# double_sided_pcb.net
KiCad netlist of a schematic drawn in EAGLE
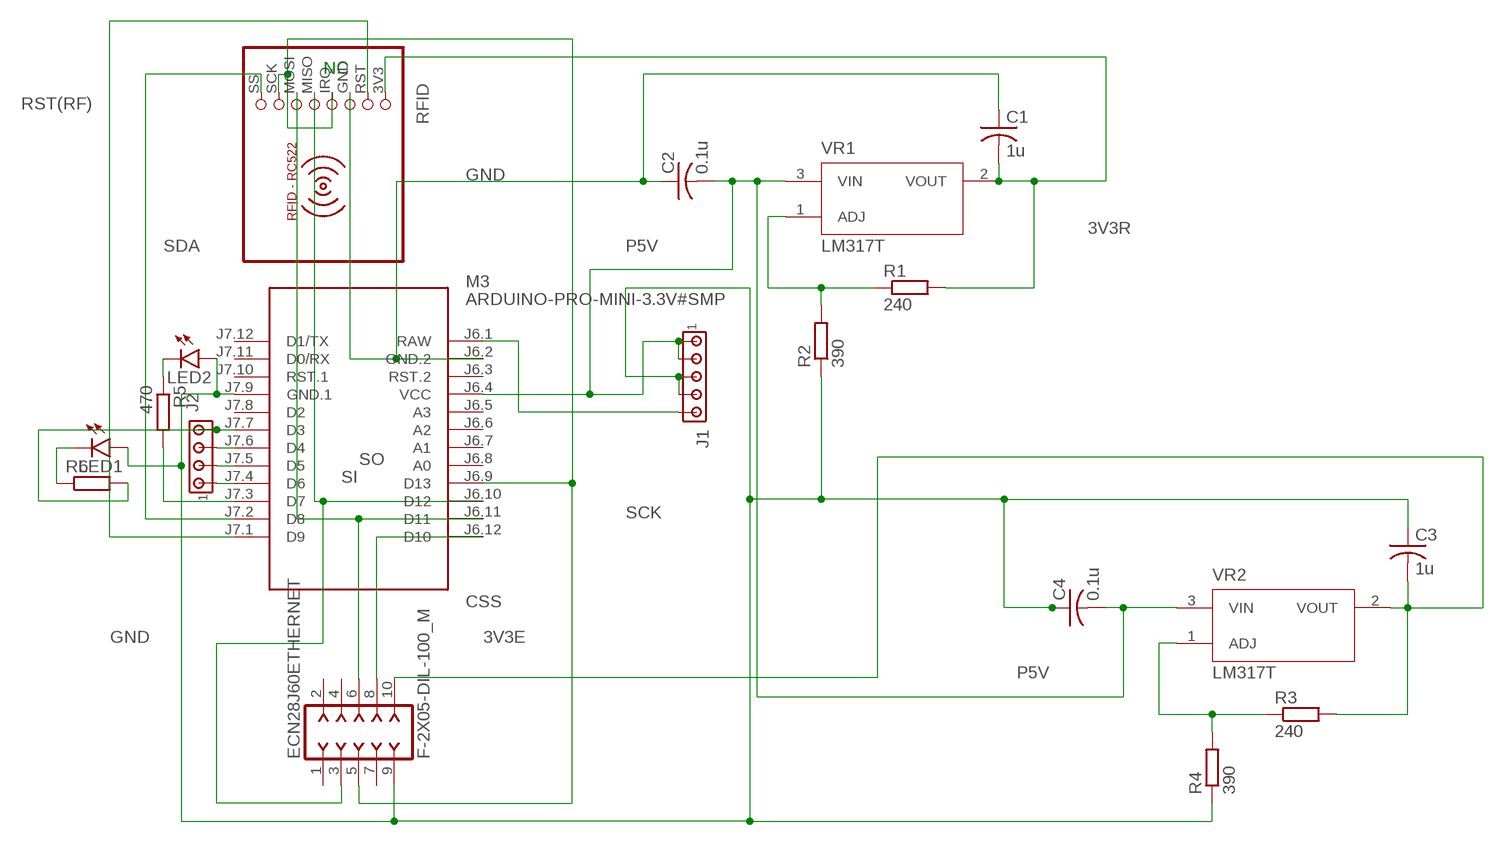
[diagram p0: schematic, sheet 1]

(export (version "E")
  (design (tool "Eeschema 10.0.6"))
  (components
    (comp (ref "C1")
      (value "1u")
      (footprint "eagle-import:C025-025X050")
      (libsource (lib "eagle-import") (part "C-US025-025X050"))
    )
    (comp (ref "C2")
      (value "0.1u")
      (footprint "eagle-import:C025-025X050")
      (libsource (lib "eagle-import") (part "C-US025-025X050"))
    )
    (comp (ref "C3")
      (value "1u")
      (footprint "eagle-import:C025-025X050")
      (libsource (lib "eagle-import") (part "C-US025-025X050"))
    )
    (comp (ref "C4")
      (value "0.1u")
      (footprint "eagle-import:C025-025X050")
      (libsource (lib "eagle-import") (part "C-US025-025X050"))
    )
    (comp (ref "ECN28J60ETHERNET")
      (value "F-2X05-DIL-100_M")
      (footprint "eagle-import:DIL-100-2X05_M")
      (libsource (lib "eagle-import") (part "F-2X05-DIL-100_M"))
    )
    (comp (ref "J1")
      (value "MTA05-100")
      (footprint "eagle-import:10X05MTA")
      (libsource (lib "eagle-import") (part "MTA05-100"))
    )
    (comp (ref "J2")
      (value "MTA04-100")
      (footprint "eagle-import:10X04MTA")
      (libsource (lib "eagle-import") (part "MTA04-100"))
    )
    (comp (ref "LED1")
      (value "LED3MM")
      (footprint "eagle-import:LED3MM")
      (libsource (lib "eagle-import") (part "LED3MM"))
    )
    (comp (ref "LED2")
      (value "LED3MM")
      (footprint "eagle-import:LED3MM")
      (libsource (lib "eagle-import") (part "LED3MM"))
    )
    (comp (ref "M3")
      (value "ARDUINO-PRO-MINI-3.3V#SMP")
      (footprint "eagle-import:ARDUINO-PRO-MINI#SMP")
      (libsource (lib "eagle-import") (part "ARDUINO-PRO-MINI-#SMP3.3V"))
    )
    (comp (ref "R1")
      (value "240")
      (footprint "eagle-import:0207_10")
      (libsource (lib "eagle-import") (part "R-EU_0207/10"))
    )
    (comp (ref "R2")
      (value "390")
      (footprint "eagle-import:0207_10")
      (libsource (lib "eagle-import") (part "R-EU_0207/10"))
    )
    (comp (ref "R3")
      (value "240")
      (footprint "eagle-import:0207_10")
      (libsource (lib "eagle-import") (part "R-EU_0207/10"))
    )
    (comp (ref "R4")
      (value "390")
      (footprint "eagle-import:0207_10")
      (libsource (lib "eagle-import") (part "R-EU_0207/10"))
    )
    (comp (ref "R5")
      (value "470")
      (footprint "eagle-import:0207_10")
      (libsource (lib "eagle-import") (part "R-EU_0207/10"))
    )
    (comp (ref "R6")
      (value "R-EU_0207/10")
      (footprint "eagle-import:0207_10")
      (libsource (lib "eagle-import") (part "R-EU_0207/10"))
    )
    (comp (ref "RFID")
      (value "RFID-RC522")
      (footprint "eagle-import:RFID-RC522")
      (libsource (lib "eagle-import") (part "RFID-RC522"))
    )
    (comp (ref "VR1")
      (value "LM317T")
      (footprint "eagle-import:TO254P1054X470X1955-3")
      (fields (field (name "MF") "Texas Instruments"))
      (libsource (lib "eagle-import") (part "LM317T"))
    )
    (comp (ref "VR2")
      (value "LM317T")
      (footprint "eagle-import:TO254P1054X470X1955-3")
      (fields (field (name "MF") "Texas Instruments"))
      (libsource (lib "eagle-import") (part "LM317T"))
    )
  )
  (nets
    (net (code "1") (name "/3V3E") (class "Default")
      (node (ref "C3") (pin "2") (pinfunction "2_2") (pintype "passive"))
      (node (ref "ECN28J60ETHERNET") (pin "10") (pinfunction "10_10") (pintype "passive"))
      (node (ref "R3") (pin "2") (pinfunction "2_2") (pintype "passive"))
      (node (ref "VR2") (pin "2") (pinfunction "VOUT_2") (pintype "output"))
    )
    (net (code "2") (name "/3V3R") (class "Default")
      (node (ref "C1") (pin "2") (pinfunction "2_2") (pintype "passive"))
      (node (ref "R1") (pin "2") (pinfunction "2_2") (pintype "passive"))
      (node (ref "RFID") (pin "3V3") (pinfunction "1_3V3") (pintype "passive"))
      (node (ref "VR1") (pin "2") (pinfunction "VOUT_2") (pintype "output"))
    )
    (net (code "3") (name "/CSS") (class "Default")
      (node (ref "ECN28J60ETHERNET") (pin "8") (pinfunction "8_8") (pintype "passive"))
      (node (ref "M3") (pin "J6.12") (pinfunction "D10_J6.12") (pintype "bidirectional"))
    )
    (net (code "4") (name "/GND") (class "Default")
      (node (ref "C1") (pin "1") (pinfunction "1_1") (pintype "passive"))
      (node (ref "C2") (pin "1") (pinfunction "1_1") (pintype "passive"))
      (node (ref "C3") (pin "1") (pinfunction "1_1") (pintype "passive"))
      (node (ref "C4") (pin "1") (pinfunction "1_1") (pintype "passive"))
      (node (ref "ECN28J60ETHERNET") (pin "9") (pinfunction "9_9") (pintype "passive"))
      (node (ref "J1") (pin "3") (pinfunction "3_3") (pintype "passive"))
      (node (ref "J1") (pin "4") (pinfunction "4_4") (pintype "passive"))
      (node (ref "LED1") (pin "A") (pinfunction "A_A") (pintype "passive"))
      (node (ref "LED2") (pin "A") (pinfunction "A_A") (pintype "passive"))
      (node (ref "M3") (pin "J6.2") (pinfunction "GND.2_J6.2") (pintype "power_in"))
      (node (ref "M3") (pin "J7.9") (pinfunction "GND.1_J7.9") (pintype "power_in"))
      (node (ref "R2") (pin "1") (pinfunction "1_1") (pintype "passive"))
      (node (ref "R4") (pin "1") (pinfunction "1_1") (pintype "passive"))
      (node (ref "RFID") (pin "GND") (pinfunction "3_GND") (pintype "passive"))
    )
    (net (code "5") (name "/P5V") (class "Default")
      (node (ref "C2") (pin "2") (pinfunction "2_2") (pintype "passive"))
      (node (ref "C4") (pin "2") (pinfunction "2_2") (pintype "passive"))
      (node (ref "J1") (pin "1") (pinfunction "1_1") (pintype "passive"))
      (node (ref "J1") (pin "2") (pinfunction "2_2") (pintype "passive"))
      (node (ref "M3") (pin "J6.4") (pinfunction "VCC_J6.4") (pintype "power_in"))
      (node (ref "VR1") (pin "3") (pinfunction "VIN_3") (pintype "input"))
      (node (ref "VR2") (pin "3") (pinfunction "VIN_3") (pintype "input"))
    )
    (net (code "6") (name "/RST(RF)") (class "Default")
      (node (ref "M3") (pin "J7.1") (pinfunction "D9_J7.1") (pintype "bidirectional"))
      (node (ref "RFID") (pin "RST") (pinfunction "2_RST") (pintype "passive"))
    )
    (net (code "7") (name "/SCK") (class "Default")
      (node (ref "ECN28J60ETHERNET") (pin "5") (pinfunction "5_5") (pintype "passive"))
      (node (ref "M3") (pin "J6.9") (pinfunction "D13_J6.9") (pintype "bidirectional"))
      (node (ref "RFID") (pin "IRQ") (pinfunction "4_IRQ") (pintype "passive"))
      (node (ref "RFID") (pin "SCK") (pinfunction "7_SCK") (pintype "passive"))
    )
    (net (code "8") (name "/SDA") (class "Default")
      (node (ref "M3") (pin "J7.2") (pinfunction "D8_J7.2") (pintype "bidirectional"))
      (node (ref "RFID") (pin "SS") (pinfunction "8_SS") (pintype "passive"))
    )
    (net (code "9") (name "/SI") (class "Default")
      (node (ref "ECN28J60ETHERNET") (pin "6") (pinfunction "6_6") (pintype "passive"))
      (node (ref "M3") (pin "J6.11") (pinfunction "D11_J6.11") (pintype "bidirectional"))
      (node (ref "RFID") (pin "MOSI") (pinfunction "6_MOSI") (pintype "passive"))
    )
    (net (code "10") (name "/SO") (class "Default")
      (node (ref "ECN28J60ETHERNET") (pin "3") (pinfunction "3_3") (pintype "passive"))
      (node (ref "M3") (pin "J6.10") (pinfunction "D12_J6.10") (pintype "bidirectional"))
      (node (ref "RFID") (pin "MISO") (pinfunction "5_MISO") (pintype "passive"))
    )
    (net (code "11") (name "Net-(LED1-C)") (class "Default")
      (node (ref "LED1") (pin "K") (pinfunction "C_K") (pintype "passive"))
      (node (ref "R6") (pin "1") (pinfunction "1_1") (pintype "passive"))
    )
    (net (code "12") (name "Net-(LED2-C)") (class "Default")
      (node (ref "LED2") (pin "K") (pinfunction "C_K") (pintype "passive"))
      (node (ref "R5") (pin "1") (pinfunction "1_1") (pintype "passive"))
    )
    (net (code "13") (name "Net-(M3-D3)") (class "Default")
      (node (ref "J2") (pin "4") (pinfunction "4_4") (pintype "passive"))
      (node (ref "M3") (pin "J7.7") (pinfunction "D3_J7.7") (pintype "bidirectional"))
      (node (ref "R6") (pin "2") (pinfunction "2_2") (pintype "passive"))
    )
    (net (code "14") (name "Net-(M3-D4)") (class "Default")
      (node (ref "J2") (pin "3") (pinfunction "3_3") (pintype "passive"))
      (node (ref "M3") (pin "J7.6") (pinfunction "D4_J7.6") (pintype "bidirectional"))
    )
    (net (code "15") (name "Net-(M3-D5)") (class "Default")
      (node (ref "J2") (pin "2") (pinfunction "2_2") (pintype "passive"))
      (node (ref "M3") (pin "J7.5") (pinfunction "D5_J7.5") (pintype "bidirectional"))
    )
    (net (code "16") (name "Net-(M3-D6)") (class "Default")
      (node (ref "J2") (pin "1") (pinfunction "1_1") (pintype "passive"))
      (node (ref "M3") (pin "J7.4") (pinfunction "D6_J7.4") (pintype "bidirectional"))
    )
    (net (code "17") (name "Net-(M3-D7)") (class "Default")
      (node (ref "M3") (pin "J7.3") (pinfunction "D7_J7.3") (pintype "bidirectional"))
      (node (ref "R5") (pin "2") (pinfunction "2_2") (pintype "passive"))
    )
    (net (code "18") (name "Net-(M3-RAW)") (class "Default")
      (node (ref "J1") (pin "5") (pinfunction "5_5") (pintype "passive"))
      (node (ref "M3") (pin "J6.1") (pinfunction "RAW_J6.1") (pintype "power_in"))
    )
    (net (code "19") (name "Net-(VR1-ADJ)") (class "Default")
      (node (ref "R1") (pin "1") (pinfunction "1_1") (pintype "passive"))
      (node (ref "R2") (pin "2") (pinfunction "2_2") (pintype "passive"))
      (node (ref "VR1") (pin "1") (pinfunction "ADJ_1") (pintype "input"))
    )
    (net (code "20") (name "Net-(VR2-ADJ)") (class "Default")
      (node (ref "R3") (pin "1") (pinfunction "1_1") (pintype "passive"))
      (node (ref "R4") (pin "2") (pinfunction "2_2") (pintype "passive"))
      (node (ref "VR2") (pin "1") (pinfunction "ADJ_1") (pintype "input"))
    )
    (net (code "21") (name "unconnected-(ECN28J60ETHERNET-Pad1)") (class "Default")
      (node (ref "ECN28J60ETHERNET") (pin "1") (pinfunction "1_1") (pintype "passive"))
    )
    (net (code "22") (name "unconnected-(ECN28J60ETHERNET-Pad2)") (class "Default")
      (node (ref "ECN28J60ETHERNET") (pin "2") (pinfunction "2_2") (pintype "passive"))
    )
    (net (code "23") (name "unconnected-(ECN28J60ETHERNET-Pad4)") (class "Default")
      (node (ref "ECN28J60ETHERNET") (pin "4") (pinfunction "4_4") (pintype "passive"))
    )
    (net (code "24") (name "unconnected-(ECN28J60ETHERNET-Pad7)") (class "Default")
      (node (ref "ECN28J60ETHERNET") (pin "7") (pinfunction "7_7") (pintype "passive"))
    )
    (net (code "25") (name "unconnected-(M3-A0-PadJ6.8)") (class "Default")
      (node (ref "M3") (pin "J6.8") (pinfunction "A0_J6.8") (pintype "bidirectional"))
    )
    (net (code "26") (name "unconnected-(M3-A1-PadJ6.7)") (class "Default")
      (node (ref "M3") (pin "J6.7") (pinfunction "A1_J6.7") (pintype "bidirectional"))
    )
    (net (code "27") (name "unconnected-(M3-A2-PadJ6.6)") (class "Default")
      (node (ref "M3") (pin "J6.6") (pinfunction "A2_J6.6") (pintype "bidirectional"))
    )
    (net (code "28") (name "unconnected-(M3-A3-PadJ6.5)") (class "Default")
      (node (ref "M3") (pin "J6.5") (pinfunction "A3_J6.5") (pintype "bidirectional"))
    )
    (net (code "29") (name "unconnected-(M3-D0{slash}RX-PadJ7.11)") (class "Default")
      (node (ref "M3") (pin "J7.11") (pinfunction "D0/RX_J7.11") (pintype "bidirectional"))
    )
    (net (code "30") (name "unconnected-(M3-D1{slash}TX-PadJ7.12)") (class "Default")
      (node (ref "M3") (pin "J7.12") (pinfunction "D1/TX_J7.12") (pintype "bidirectional"))
    )
    (net (code "31") (name "unconnected-(M3-D2-PadJ7.8)") (class "Default")
      (node (ref "M3") (pin "J7.8") (pinfunction "D2_J7.8") (pintype "bidirectional"))
    )
    (net (code "32") (name "unconnected-(M3-RST.1-PadJ7.10)") (class "Default")
      (node (ref "M3") (pin "J7.10") (pinfunction "RST.1_J7.10") (pintype "bidirectional"))
    )
    (net (code "33") (name "unconnected-(M3-RST.2-PadJ6.3)") (class "Default")
      (node (ref "M3") (pin "J6.3") (pinfunction "RST.2_J6.3") (pintype "bidirectional"))
    )
  )
)
